# Stereo_RDS_Encoder-Digital_Board.net
KiCad netlist of a schematic drawn in EAGLE
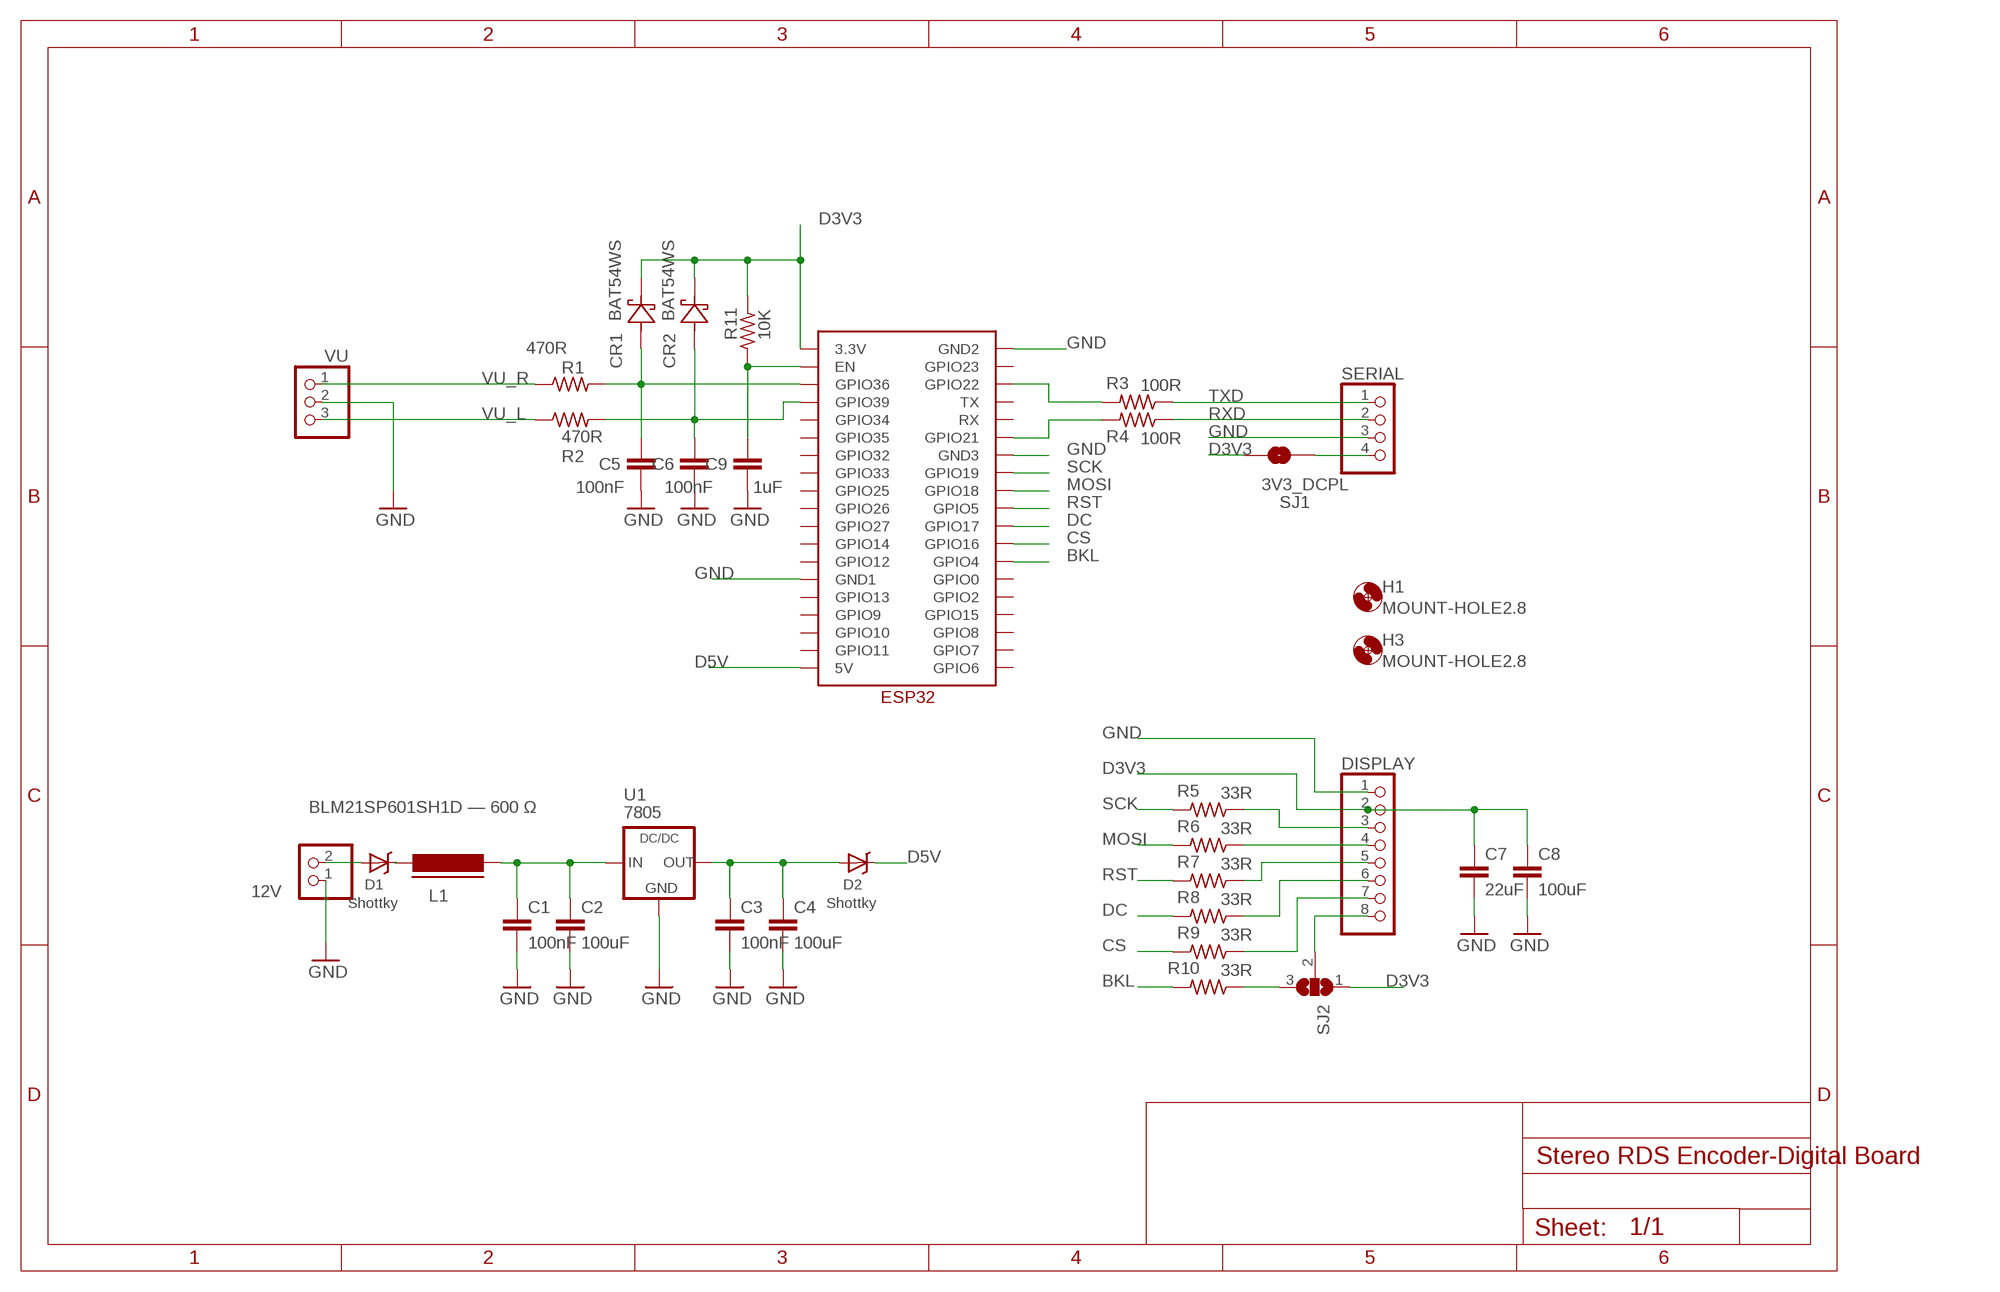
[diagram p0: schematic, sheet 1]

(export (version "E")
  (design (tool "Eeschema 10.0.6"))
  (components
    (comp (ref "12V")
      (value "PINHD-1X2")
      (footprint "eagle-import:1X02")
      (libsource (lib "eagle-import") (part "PINHD-1X2"))
    )
    (comp (ref "C1")
      (value "100nF")
      (footprint "eagle-import:C0805")
      (libsource (lib "eagle-import") (part "C-EUC0805"))
    )
    (comp (ref "C2")
      (value "100uF")
      (footprint "eagle-import:C0805")
      (libsource (lib "eagle-import") (part "C-EUC0805"))
    )
    (comp (ref "C3")
      (value "100nF")
      (footprint "eagle-import:C0805")
      (libsource (lib "eagle-import") (part "C-EUC0805"))
    )
    (comp (ref "C4")
      (value "100uF")
      (footprint "eagle-import:C0805")
      (libsource (lib "eagle-import") (part "C-EUC0805"))
    )
    (comp (ref "C5")
      (value "100nF")
      (footprint "eagle-import:C0805")
      (libsource (lib "eagle-import") (part "C-EUC0805"))
    )
    (comp (ref "C6")
      (value "100nF")
      (footprint "eagle-import:C0805")
      (libsource (lib "eagle-import") (part "C-EUC0805"))
    )
    (comp (ref "C7")
      (value "22uF")
      (footprint "eagle-import:C0805")
      (libsource (lib "eagle-import") (part "C-EUC0805"))
    )
    (comp (ref "C8")
      (value "100uF")
      (footprint "eagle-import:C0805")
      (libsource (lib "eagle-import") (part "C-EUC0805"))
    )
    (comp (ref "C9")
      (value "1uF")
      (footprint "eagle-import:C0805")
      (libsource (lib "eagle-import") (part "C-EUC0805"))
    )
    (comp (ref "CR1")
      (value "BAT54WS")
      (footprint "eagle-import:SDO_SOD-323_VIS")
      (fields
        (field (name "MANUFACTURER_PART_NUMBER") "BAT54WS-E3-18")
        (field (name "COPYRIGHT") "Copyright (C) 2025 Ultra Librarian. All rights reserved.")
      )
      (libsource (lib "eagle-import") (part "BAT54WS-E3-18"))
    )
    (comp (ref "CR2")
      (value "BAT54WS")
      (footprint "eagle-import:SDO_SOD-323_VIS")
      (fields
        (field (name "MANUFACTURER_PART_NUMBER") "BAT54WS-E3-18")
        (field (name "COPYRIGHT") "Copyright (C) 2025 Ultra Librarian. All rights reserved.")
      )
      (libsource (lib "eagle-import") (part "BAT54WS-E3-18"))
    )
    (comp (ref "D1")
      (value "Shottky")
      (footprint "eagle-import:SMA-403D")
      (libsource (lib "eagle-import") (part "DIODE-SCHOTTKYSMA-403D"))
    )
    (comp (ref "D2")
      (value "Shottky")
      (footprint "eagle-import:SMA-403D")
      (libsource (lib "eagle-import") (part "DIODE-SCHOTTKYSMA-403D"))
    )
    (comp (ref "DEV1")
      (value "ESP32")
      (footprint "eagle-import:ESP32")
      (libsource (lib "eagle-import") (part "ESP32"))
    )
    (comp (ref "DISPLAY")
      (value "PINHD-1X8")
      (footprint "eagle-import:1X08")
      (libsource (lib "eagle-import") (part "PINHD-1X8"))
    )
    (comp (ref "H1")
      (value "MOUNT-HOLE2.8")
      (footprint "eagle-import:2,8")
      (libsource (lib "eagle-import") (part "MOUNT-HOLE2.8"))
    )
    (comp (ref "H3")
      (value "MOUNT-HOLE2.8")
      (footprint "eagle-import:2,8")
      (libsource (lib "eagle-import") (part "MOUNT-HOLE2.8"))
    )
    (comp (ref "L1")
      (value "BLM21SP601SH1D — 600 Ω")
      (footprint "eagle-import:FB805")
      (libsource (lib "eagle-import") (part "FERRITE-0805"))
    )
    (comp (ref "R1")
      (value "470R")
      (footprint "eagle-import:M0805")
      (libsource (lib "eagle-import") (part "R-US_M0805"))
    )
    (comp (ref "R2")
      (value "470R")
      (footprint "eagle-import:M0805")
      (libsource (lib "eagle-import") (part "R-US_M0805"))
    )
    (comp (ref "R3")
      (value "100R")
      (footprint "eagle-import:M0805")
      (libsource (lib "eagle-import") (part "R-US_M0805"))
    )
    (comp (ref "R4")
      (value "100R")
      (footprint "eagle-import:M0805")
      (libsource (lib "eagle-import") (part "R-US_M0805"))
    )
    (comp (ref "R5")
      (value "33R")
      (footprint "eagle-import:M0805")
      (libsource (lib "eagle-import") (part "R-US_M0805"))
    )
    (comp (ref "R6")
      (value "33R")
      (footprint "eagle-import:M0805")
      (libsource (lib "eagle-import") (part "R-US_M0805"))
    )
    (comp (ref "R7")
      (value "33R")
      (footprint "eagle-import:M0805")
      (libsource (lib "eagle-import") (part "R-US_M0805"))
    )
    (comp (ref "R8")
      (value "33R")
      (footprint "eagle-import:M0805")
      (libsource (lib "eagle-import") (part "R-US_M0805"))
    )
    (comp (ref "R9")
      (value "33R")
      (footprint "eagle-import:M0805")
      (libsource (lib "eagle-import") (part "R-US_M0805"))
    )
    (comp (ref "R10")
      (value "33R")
      (footprint "eagle-import:M0805")
      (libsource (lib "eagle-import") (part "R-US_M0805"))
    )
    (comp (ref "R11")
      (value "10K")
      (footprint "eagle-import:M0805")
      (libsource (lib "eagle-import") (part "R-US_M0805"))
    )
    (comp (ref "SERIAL")
      (value "PINHD-1X4")
      (footprint "eagle-import:1X04")
      (libsource (lib "eagle-import") (part "PINHD-1X4"))
    )
    (comp (ref "SJ1")
      (value "3V3_DCPL")
      (footprint "eagle-import:SJ_2S-NO")
      (libsource (lib "eagle-import") (part "SOLDERJUMPERNO"))
    )
    (comp (ref "SJ2")
      (value "SJ2W")
      (footprint "eagle-import:SJ_2")
      (libsource (lib "eagle-import") (part "SJ2W"))
    )
    (comp (ref "U1")
      (value "7805")
      (footprint "eagle-import:R-78XX")
      (libsource (lib "eagle-import") (part "R-78XX"))
    )
    (comp (ref "VU")
      (value "PINHD-1X3")
      (footprint "eagle-import:1X03")
      (libsource (lib "eagle-import") (part "PINHD-1X3"))
    )
  )
  (nets
    (net (code "1") (name "/BKL") (class "Default")
      (node (ref "DEV1") (pin "GPIO4") (pinfunction "GPIO4_GPIO4") (pintype "bidirectional"))
      (node (ref "R10") (pin "2") (pinfunction "2_2") (pintype "passive"))
    )
    (net (code "2") (name "/CS") (class "Default")
      (node (ref "DEV1") (pin "GPIO16") (pinfunction "GPIO16_GPIO16") (pintype "bidirectional"))
      (node (ref "R9") (pin "2") (pinfunction "2_2") (pintype "passive"))
    )
    (net (code "3") (name "/D3V3") (class "Default")
      (node (ref "C7") (pin "1") (pinfunction "1_1") (pintype "passive"))
      (node (ref "C8") (pin "1") (pinfunction "1_1") (pintype "passive"))
      (node (ref "CR1") (pin "1") (pinfunction "CATHODE_1") (pintype "passive"))
      (node (ref "CR2") (pin "1") (pinfunction "CATHODE_1") (pintype "passive"))
      (node (ref "DEV1") (pin "3.3V") (pinfunction "3.3V_3.3V") (pintype "bidirectional"))
      (node (ref "DISPLAY") (pin "2") (pinfunction "2_2") (pintype "passive"))
      (node (ref "R11") (pin "2") (pinfunction "2_2") (pintype "passive"))
      (node (ref "SJ1") (pin "1") (pinfunction "1_1") (pintype "passive"))
      (node (ref "SJ2") (pin "1") (pinfunction "1_1") (pintype "passive"))
    )
    (net (code "4") (name "/D5V") (class "Default")
      (node (ref "D2") (pin "C") (pinfunction "C_C") (pintype "passive"))
      (node (ref "DEV1") (pin "5V") (pinfunction "5V_5V") (pintype "bidirectional"))
    )
    (net (code "5") (name "/DC") (class "Default")
      (node (ref "DEV1") (pin "GPIO17") (pinfunction "GPIO17_GPIO17") (pintype "bidirectional"))
      (node (ref "R8") (pin "2") (pinfunction "2_2") (pintype "passive"))
    )
    (net (code "6") (name "/MOSI") (class "Default")
      (node (ref "DEV1") (pin "GPIO18") (pinfunction "GPIO18_GPIO18") (pintype "bidirectional"))
      (node (ref "R6") (pin "2") (pinfunction "2_2") (pintype "passive"))
    )
    (net (code "7") (name "/RST") (class "Default")
      (node (ref "DEV1") (pin "GPIO5") (pinfunction "GPIO5_GPIO5") (pintype "bidirectional"))
      (node (ref "R7") (pin "2") (pinfunction "2_2") (pintype "passive"))
    )
    (net (code "8") (name "/RXD") (class "Default")
      (node (ref "R4") (pin "1") (pinfunction "1_1") (pintype "passive"))
      (node (ref "SERIAL") (pin "2") (pinfunction "2_2") (pintype "passive"))
    )
    (net (code "9") (name "/SCK") (class "Default")
      (node (ref "DEV1") (pin "GPIO19") (pinfunction "GPIO19_GPIO19") (pintype "bidirectional"))
      (node (ref "R5") (pin "2") (pinfunction "2_2") (pintype "passive"))
    )
    (net (code "10") (name "/TXD") (class "Default")
      (node (ref "R3") (pin "1") (pinfunction "1_1") (pintype "passive"))
      (node (ref "SERIAL") (pin "1") (pinfunction "1_1") (pintype "passive"))
    )
    (net (code "11") (name "/VU_L") (class "Default")
      (node (ref "R2") (pin "1") (pinfunction "1_1") (pintype "passive"))
      (node (ref "VU") (pin "3") (pinfunction "3_3") (pintype "passive"))
    )
    (net (code "12") (name "/VU_R") (class "Default")
      (node (ref "R1") (pin "1") (pinfunction "1_1") (pintype "passive"))
      (node (ref "VU") (pin "1") (pinfunction "1_1") (pintype "passive"))
    )
    (net (code "13") (name "GND") (class "Default")
      (node (ref "12V") (pin "1") (pinfunction "1_1") (pintype "passive"))
      (node (ref "C1") (pin "2") (pinfunction "2_2") (pintype "passive"))
      (node (ref "C2") (pin "2") (pinfunction "2_2") (pintype "passive"))
      (node (ref "C3") (pin "2") (pinfunction "2_2") (pintype "passive"))
      (node (ref "C4") (pin "2") (pinfunction "2_2") (pintype "passive"))
      (node (ref "C5") (pin "2") (pinfunction "2_2") (pintype "passive"))
      (node (ref "C6") (pin "2") (pinfunction "2_2") (pintype "passive"))
      (node (ref "C7") (pin "2") (pinfunction "2_2") (pintype "passive"))
      (node (ref "C8") (pin "2") (pinfunction "2_2") (pintype "passive"))
      (node (ref "C9") (pin "2") (pinfunction "2_2") (pintype "passive"))
      (node (ref "DEV1") (pin "GND1") (pinfunction "GND1_GND1") (pintype "bidirectional"))
      (node (ref "DEV1") (pin "GND2") (pinfunction "GND2_GND2") (pintype "bidirectional"))
      (node (ref "DEV1") (pin "GND3") (pinfunction "GND3_GND3") (pintype "bidirectional"))
      (node (ref "DISPLAY") (pin "1") (pinfunction "1_1") (pintype "passive"))
      (node (ref "SERIAL") (pin "3") (pinfunction "3_3") (pintype "passive"))
      (node (ref "U1") (pin "2") (pinfunction "GND_2") (pintype "input"))
      (node (ref "VU") (pin "2") (pinfunction "2_2") (pintype "passive"))
    )
    (net (code "14") (name "Net-(12V-Pad2)") (class "Default")
      (node (ref "12V") (pin "2") (pinfunction "2_2") (pintype "passive"))
      (node (ref "D1") (pin "A") (pinfunction "A_A") (pintype "passive"))
    )
    (net (code "15") (name "Net-(C9-Pad1)") (class "Default")
      (node (ref "C9") (pin "1") (pinfunction "1_1") (pintype "passive"))
      (node (ref "DEV1") (pin "EN") (pinfunction "EN_EN") (pintype "bidirectional"))
      (node (ref "R11") (pin "1") (pinfunction "1_1") (pintype "passive"))
    )
    (net (code "16") (name "Net-(CR1-ANODE)") (class "Default")
      (node (ref "C5") (pin "1") (pinfunction "1_1") (pintype "passive"))
      (node (ref "CR1") (pin "2") (pinfunction "ANODE_2") (pintype "passive"))
      (node (ref "DEV1") (pin "GPIO36") (pinfunction "GPIO36_GPIO36") (pintype "bidirectional"))
      (node (ref "R1") (pin "2") (pinfunction "2_2") (pintype "passive"))
    )
    (net (code "17") (name "Net-(CR2-ANODE)") (class "Default")
      (node (ref "C6") (pin "1") (pinfunction "1_1") (pintype "passive"))
      (node (ref "CR2") (pin "2") (pinfunction "ANODE_2") (pintype "passive"))
      (node (ref "DEV1") (pin "GPIO39") (pinfunction "GPIO39_GPIO39") (pintype "bidirectional"))
      (node (ref "R2") (pin "2") (pinfunction "2_2") (pintype "passive"))
    )
    (net (code "18") (name "Net-(D1-PadC)") (class "Default")
      (node (ref "D1") (pin "C") (pinfunction "C_C") (pintype "passive"))
      (node (ref "L1") (pin "1") (pinfunction "1_1") (pintype "passive"))
    )
    (net (code "19") (name "Net-(DEV1-PadGPIO21)") (class "Default")
      (node (ref "DEV1") (pin "GPIO21") (pinfunction "GPIO21_GPIO21") (pintype "bidirectional"))
      (node (ref "R4") (pin "2") (pinfunction "2_2") (pintype "passive"))
    )
    (net (code "20") (name "Net-(DEV1-PadGPIO22)") (class "Default")
      (node (ref "DEV1") (pin "GPIO22") (pinfunction "GPIO22_GPIO22") (pintype "bidirectional"))
      (node (ref "R3") (pin "2") (pinfunction "2_2") (pintype "passive"))
    )
    (net (code "21") (name "Net-(DISPLAY-Pad3)") (class "Default")
      (node (ref "DISPLAY") (pin "3") (pinfunction "3_3") (pintype "passive"))
      (node (ref "R5") (pin "1") (pinfunction "1_1") (pintype "passive"))
    )
    (net (code "22") (name "Net-(DISPLAY-Pad4)") (class "Default")
      (node (ref "DISPLAY") (pin "4") (pinfunction "4_4") (pintype "passive"))
      (node (ref "R6") (pin "1") (pinfunction "1_1") (pintype "passive"))
    )
    (net (code "23") (name "Net-(DISPLAY-Pad5)") (class "Default")
      (node (ref "DISPLAY") (pin "5") (pinfunction "5_5") (pintype "passive"))
      (node (ref "R7") (pin "1") (pinfunction "1_1") (pintype "passive"))
    )
    (net (code "24") (name "Net-(DISPLAY-Pad6)") (class "Default")
      (node (ref "DISPLAY") (pin "6") (pinfunction "6_6") (pintype "passive"))
      (node (ref "R8") (pin "1") (pinfunction "1_1") (pintype "passive"))
    )
    (net (code "25") (name "Net-(DISPLAY-Pad7)") (class "Default")
      (node (ref "DISPLAY") (pin "7") (pinfunction "7_7") (pintype "passive"))
      (node (ref "R9") (pin "1") (pinfunction "1_1") (pintype "passive"))
    )
    (net (code "26") (name "Net-(DISPLAY-Pad8)") (class "Default")
      (node (ref "DISPLAY") (pin "8") (pinfunction "8_8") (pintype "passive"))
      (node (ref "SJ2") (pin "2") (pinfunction "2_2") (pintype "passive"))
    )
    (net (code "27") (name "Net-(R10-Pad1)") (class "Default")
      (node (ref "R10") (pin "1") (pinfunction "1_1") (pintype "passive"))
      (node (ref "SJ2") (pin "3") (pinfunction "3_3") (pintype "passive"))
    )
    (net (code "28") (name "Net-(SERIAL-Pad4)") (class "Default")
      (node (ref "SERIAL") (pin "4") (pinfunction "4_4") (pintype "passive"))
      (node (ref "SJ1") (pin "2") (pinfunction "2_2") (pintype "passive"))
    )
    (net (code "29") (name "Net-(U1-IN)") (class "Default")
      (node (ref "C1") (pin "1") (pinfunction "1_1") (pintype "passive"))
      (node (ref "C2") (pin "1") (pinfunction "1_1") (pintype "passive"))
      (node (ref "L1") (pin "2") (pinfunction "2_2") (pintype "passive"))
      (node (ref "U1") (pin "1") (pinfunction "IN_1") (pintype "input"))
    )
    (net (code "30") (name "Net-(U1-OUT)") (class "Default")
      (node (ref "C3") (pin "1") (pinfunction "1_1") (pintype "passive"))
      (node (ref "C4") (pin "1") (pinfunction "1_1") (pintype "passive"))
      (node (ref "D2") (pin "A") (pinfunction "A_A") (pintype "passive"))
      (node (ref "U1") (pin "3") (pinfunction "OUT_3") (pintype "passive"))
    )
    (net (code "31") (name "unconnected-(DEV1-PadGPIO0)") (class "Default")
      (node (ref "DEV1") (pin "GPIO0") (pinfunction "GPIO0_GPIO0") (pintype "bidirectional"))
    )
    (net (code "32") (name "unconnected-(DEV1-PadGPIO2)") (class "Default")
      (node (ref "DEV1") (pin "GPIO2") (pinfunction "GPIO2_GPIO2") (pintype "bidirectional"))
    )
    (net (code "33") (name "unconnected-(DEV1-PadGPIO6)") (class "Default")
      (node (ref "DEV1") (pin "GPIO6") (pinfunction "GPIO6_GPIO6") (pintype "bidirectional"))
    )
    (net (code "34") (name "unconnected-(DEV1-PadGPIO7)") (class "Default")
      (node (ref "DEV1") (pin "GPIO7") (pinfunction "GPIO7_GPIO7") (pintype "bidirectional"))
    )
    (net (code "35") (name "unconnected-(DEV1-PadGPIO8)") (class "Default")
      (node (ref "DEV1") (pin "GPIO8") (pinfunction "GPIO8_GPIO8") (pintype "bidirectional"))
    )
    (net (code "36") (name "unconnected-(DEV1-PadGPIO9)") (class "Default")
      (node (ref "DEV1") (pin "GPIO9") (pinfunction "GPIO9_GPIO9") (pintype "bidirectional"))
    )
    (net (code "37") (name "unconnected-(DEV1-PadGPIO10)") (class "Default")
      (node (ref "DEV1") (pin "GPIO10") (pinfunction "GPIO10_GPIO10") (pintype "bidirectional"))
    )
    (net (code "38") (name "unconnected-(DEV1-PadGPIO11)") (class "Default")
      (node (ref "DEV1") (pin "GPIO11") (pinfunction "GPIO11_GPIO11") (pintype "bidirectional"))
    )
    (net (code "39") (name "unconnected-(DEV1-PadGPIO12)") (class "Default")
      (node (ref "DEV1") (pin "GPIO12") (pinfunction "GPIO12_GPIO12") (pintype "bidirectional"))
    )
    (net (code "40") (name "unconnected-(DEV1-PadGPIO13)") (class "Default")
      (node (ref "DEV1") (pin "GPIO13") (pinfunction "GPIO13_GPIO13") (pintype "bidirectional"))
    )
    (net (code "41") (name "unconnected-(DEV1-PadGPIO14)") (class "Default")
      (node (ref "DEV1") (pin "GPIO14") (pinfunction "GPIO14_GPIO14") (pintype "bidirectional"))
    )
    (net (code "42") (name "unconnected-(DEV1-PadGPIO15)") (class "Default")
      (node (ref "DEV1") (pin "GPIO15") (pinfunction "GPIO15_GPIO15") (pintype "bidirectional"))
    )
    (net (code "43") (name "unconnected-(DEV1-PadGPIO23)") (class "Default")
      (node (ref "DEV1") (pin "GPIO23") (pinfunction "GPIO23_GPIO23") (pintype "bidirectional"))
    )
    (net (code "44") (name "unconnected-(DEV1-PadGPIO25)") (class "Default")
      (node (ref "DEV1") (pin "GPIO25") (pinfunction "GPIO25_GPIO25") (pintype "bidirectional"))
    )
    (net (code "45") (name "unconnected-(DEV1-PadGPIO26)") (class "Default")
      (node (ref "DEV1") (pin "GPIO26") (pinfunction "GPIO26_GPIO26") (pintype "bidirectional"))
    )
    (net (code "46") (name "unconnected-(DEV1-PadGPIO27)") (class "Default")
      (node (ref "DEV1") (pin "GPIO27") (pinfunction "GPIO27_GPIO27") (pintype "bidirectional"))
    )
    (net (code "47") (name "unconnected-(DEV1-PadGPIO32)") (class "Default")
      (node (ref "DEV1") (pin "GPIO32") (pinfunction "GPIO32_GPIO32") (pintype "bidirectional"))
    )
    (net (code "48") (name "unconnected-(DEV1-PadGPIO33)") (class "Default")
      (node (ref "DEV1") (pin "GPIO33") (pinfunction "GPIO33_GPIO33") (pintype "bidirectional"))
    )
    (net (code "49") (name "unconnected-(DEV1-PadGPIO34)") (class "Default")
      (node (ref "DEV1") (pin "GPIO34") (pinfunction "GPIO34_GPIO34") (pintype "bidirectional"))
    )
    (net (code "50") (name "unconnected-(DEV1-PadGPIO35)") (class "Default")
      (node (ref "DEV1") (pin "GPIO35") (pinfunction "GPIO35_GPIO35") (pintype "bidirectional"))
    )
    (net (code "51") (name "unconnected-(DEV1-PadRX)") (class "Default")
      (node (ref "DEV1") (pin "RX") (pinfunction "RX_RX") (pintype "bidirectional"))
    )
    (net (code "52") (name "unconnected-(DEV1-PadTX)") (class "Default")
      (node (ref "DEV1") (pin "TX") (pinfunction "TX_TX") (pintype "bidirectional"))
    )
  )
)
